# Display_Port.net
KiCad netlist of a schematic drawn in Altium Designer
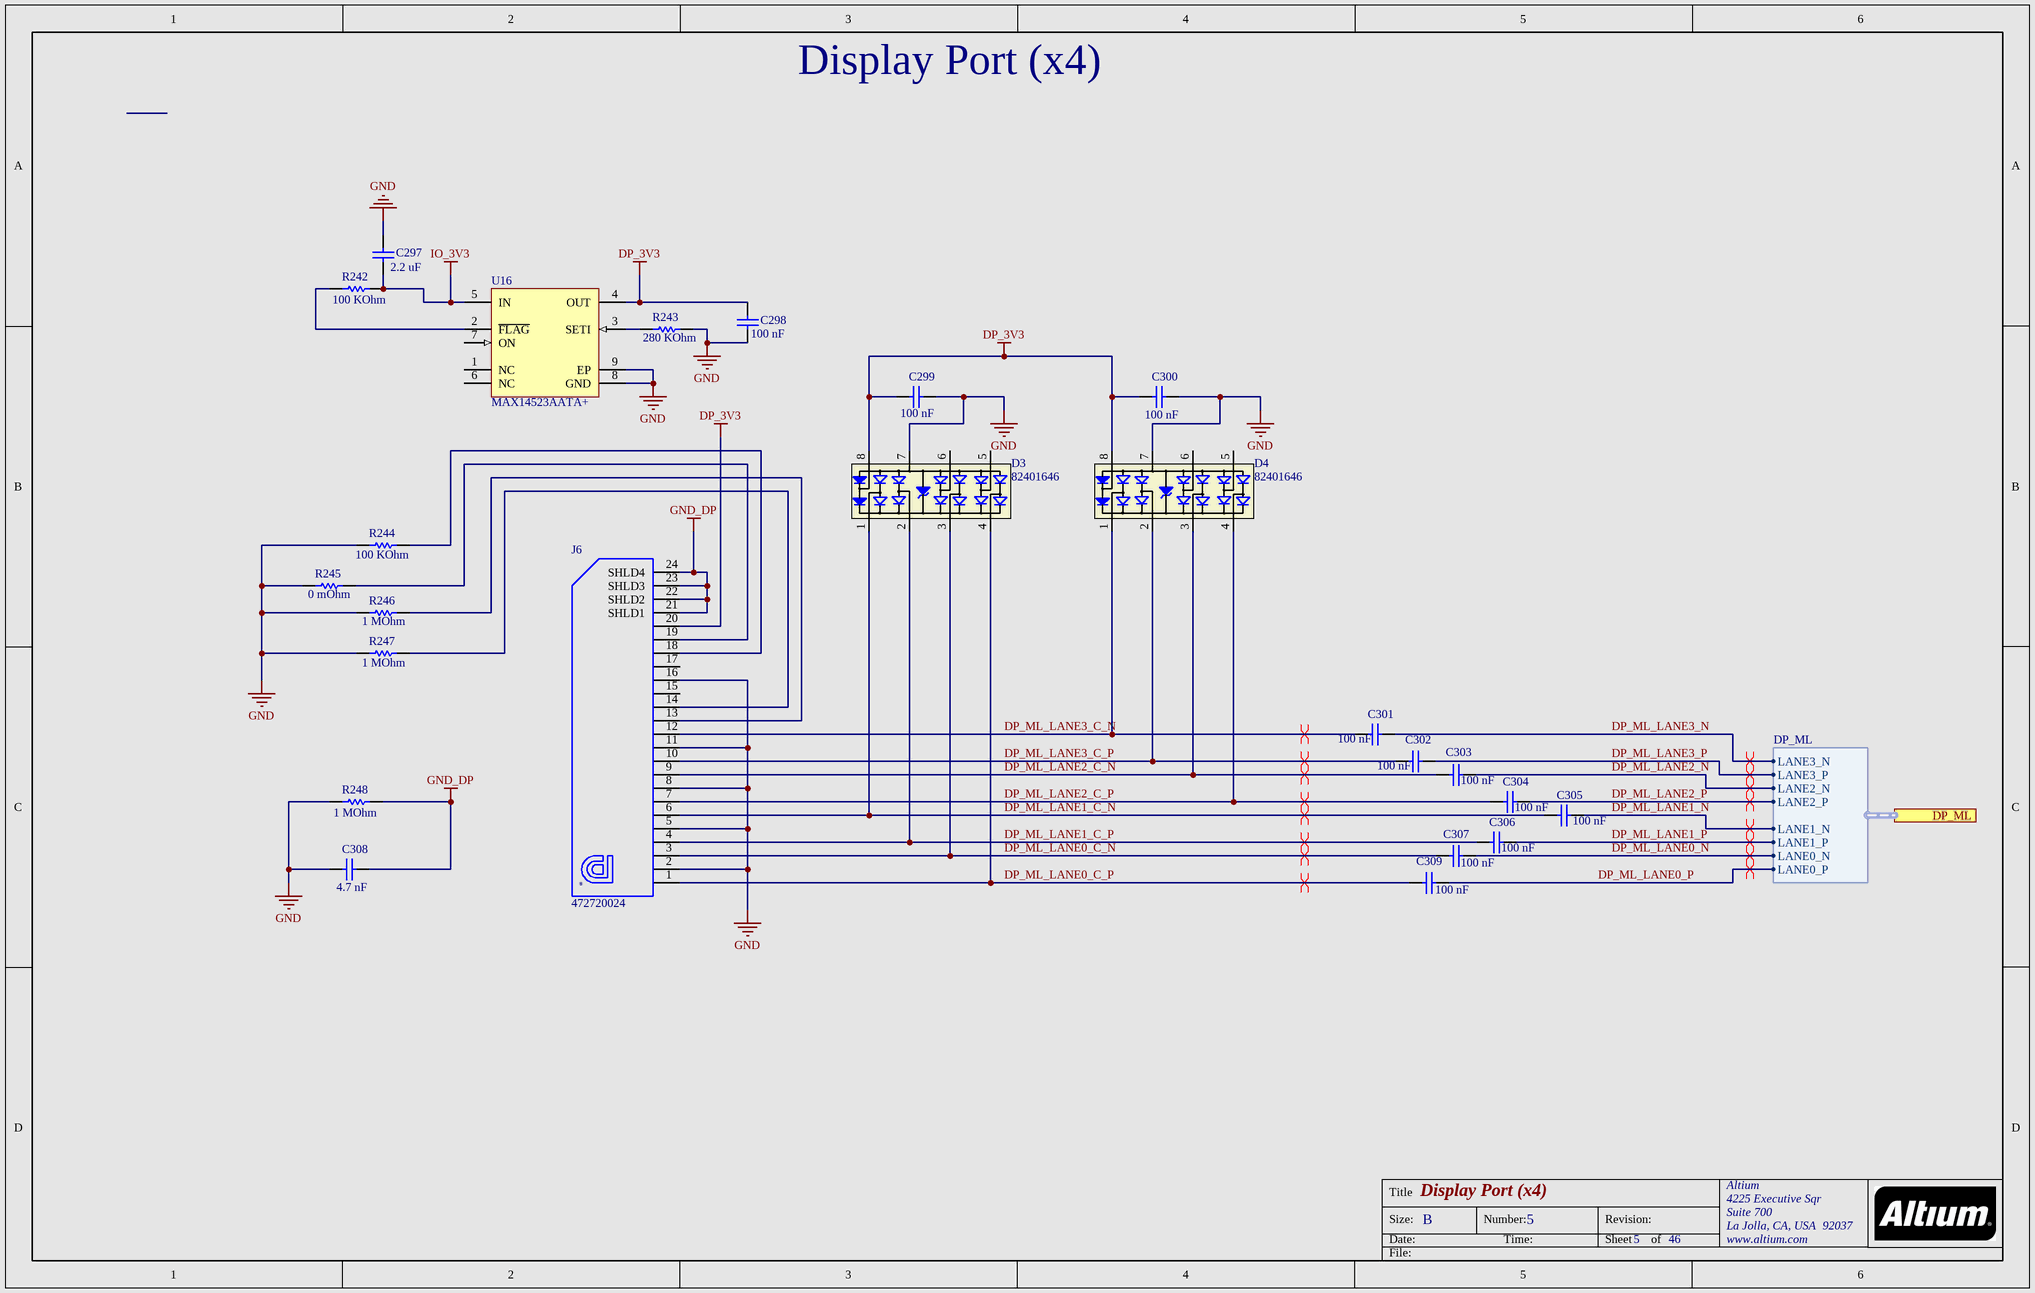
[diagram p0: Display_Port.SchDoc]

(export (version "E")
  (design (tool "Eeschema 10.0.6"))
  (components
    (comp (ref "C297")
      (value "GRM188R61A225KE34x")
      (footprint "CAPC1608X90X35ML10T15")
      (description "Chip Capacitor, 2.2 uF, +/- 10%, 10 V, -55 to 85 degC, 0603 (1608 Metric), RoHS, Tape and Reel")
      (fields (field (name "TOLERANCE") "10%") (field (name "CAPACITANCE") "2.2 uF"))
      (libsource (lib "") (part "CAP-NP-2_1"))
    )
    (comp (ref "C298")
      (value "C1005X7R1E104M")
      (footprint "CAPC1005X55X10LL05")
      (description "Chip Capacitor, 0.1 uF, +/- 20%, 25 V, -55 to 125 degC, 0402 (1005 Metric), RoHS, Tape and Reel")
      (fields (field (name "TOLERANCE") "20%") (field (name "CAPACITANCE") "100 nF"))
      (libsource (lib "Altium Content Vault") (part "CAP-NP-2"))
    )
    (comp (ref "C299")
      (value "C1005X7R1E104M")
      (footprint "CAPC1005X55X10LL05")
      (description "Chip Capacitor, 0.1 uF, +/- 20%, 25 V, -55 to 125 degC, 0402 (1005 Metric), RoHS, Tape and Reel")
      (fields (field (name "TOLERANCE") "20%") (field (name "CAPACITANCE") "100 nF"))
      (libsource (lib "Altium Content Vault") (part "CAP-NP-2"))
    )
    (comp (ref "C300")
      (value "C1005X7R1E104M")
      (footprint "CAPC1005X55X10LL05")
      (description "Chip Capacitor, 0.1 uF, +/- 20%, 25 V, -55 to 125 degC, 0402 (1005 Metric), RoHS, Tape and Reel")
      (fields (field (name "TOLERANCE") "20%") (field (name "CAPACITANCE") "100 nF"))
      (libsource (lib "Altium Content Vault") (part "CAP-NP-2"))
    )
    (comp (ref "C301")
      (value "C1005X7R1E104M")
      (footprint "CAPC1005X55X10LL05")
      (description "Chip Capacitor, 0.1 uF, +/- 20%, 25 V, -55 to 125 degC, 0402 (1005 Metric), RoHS, Tape and Reel")
      (fields (field (name "TOLERANCE") "20%") (field (name "CAPACITANCE") "100 nF"))
      (libsource (lib "Altium Content Vault") (part "CAP-NP-2"))
    )
    (comp (ref "C302")
      (value "C1005X7R1E104M")
      (footprint "CAPC1005X55X10LL05")
      (description "Chip Capacitor, 0.1 uF, +/- 20%, 25 V, -55 to 125 degC, 0402 (1005 Metric), RoHS, Tape and Reel")
      (fields (field (name "TOLERANCE") "20%") (field (name "CAPACITANCE") "100 nF"))
      (libsource (lib "Altium Content Vault") (part "CAP-NP-2"))
    )
    (comp (ref "C303")
      (value "C1005X7R1E104M")
      (footprint "CAPC1005X55X10LL05")
      (description "Chip Capacitor, 0.1 uF, +/- 20%, 25 V, -55 to 125 degC, 0402 (1005 Metric), RoHS, Tape and Reel")
      (fields (field (name "TOLERANCE") "20%") (field (name "CAPACITANCE") "100 nF"))
      (libsource (lib "Altium Content Vault") (part "CAP-NP-2"))
    )
    (comp (ref "C304")
      (value "C1005X7R1E104M")
      (footprint "CAPC1005X55X10LL05")
      (description "Chip Capacitor, 0.1 uF, +/- 20%, 25 V, -55 to 125 degC, 0402 (1005 Metric), RoHS, Tape and Reel")
      (fields (field (name "TOLERANCE") "20%") (field (name "CAPACITANCE") "100 nF"))
      (libsource (lib "Altium Content Vault") (part "CAP-NP-2"))
    )
    (comp (ref "C305")
      (value "C1005X7R1E104M")
      (footprint "CAPC1005X55X10LL05")
      (description "Chip Capacitor, 0.1 uF, +/- 20%, 25 V, -55 to 125 degC, 0402 (1005 Metric), RoHS, Tape and Reel")
      (fields (field (name "TOLERANCE") "20%") (field (name "CAPACITANCE") "100 nF"))
      (libsource (lib "Altium Content Vault") (part "CAP-NP-2"))
    )
    (comp (ref "C306")
      (value "C1005X7R1E104M")
      (footprint "CAPC1005X55X10LL05")
      (description "Chip Capacitor, 0.1 uF, +/- 20%, 25 V, -55 to 125 degC, 0402 (1005 Metric), RoHS, Tape and Reel")
      (fields (field (name "TOLERANCE") "20%") (field (name "CAPACITANCE") "100 nF"))
      (libsource (lib "Altium Content Vault") (part "CAP-NP-2"))
    )
    (comp (ref "C307")
      (value "C1005X7R1E104M")
      (footprint "CAPC1005X55X10LL05")
      (description "Chip Capacitor, 0.1 uF, +/- 20%, 25 V, -55 to 125 degC, 0402 (1005 Metric), RoHS, Tape and Reel")
      (fields (field (name "TOLERANCE") "20%") (field (name "CAPACITANCE") "100 nF"))
      (libsource (lib "Altium Content Vault") (part "CAP-NP-2"))
    )
    (comp (ref "C308")
      (value "GRM155R71H472KA01D")
      (footprint "CAPC1005X55X25NL05T10")
      (description "Chip Capacitor, 4.7 nF, +/- 10%, 50 V, -55 to 125 degC, 0402 (1005 Metric), RoHS, Tape and Reel")
      (fields
        (field (name "TOLERANCE") "10%")
        (field (name "CAPACITANCE") "4.7 nF")
        (field (name "MANUFACTURER") "Basic Passives")
      )
      (libsource (lib "Altium Content Vault") (part "CAP-NP-2"))
    )
    (comp (ref "C309")
      (value "C1005X7R1E104M")
      (footprint "CAPC1005X55X10LL05")
      (description "Chip Capacitor, 0.1 uF, +/- 20%, 25 V, -55 to 125 degC, 0402 (1005 Metric), RoHS, Tape and Reel")
      (fields (field (name "TOLERANCE") "20%") (field (name "CAPACITANCE") "100 nF"))
      (libsource (lib "Altium Content Vault") (part "CAP-NP-2"))
    )
    (comp (ref "D3")
      (value "82401646")
      (footprint "MSOP-8L")
      (description "TVS Diode WE-TVS-SS, VRWM=5V")
      (fields (field (name "MANUFACTURER") "Wuerth Elektronik"))
      (libsource (lib "Altium Content Vault") (part "CMP-1482-00002-1"))
    )
    (comp (ref "D4")
      (value "82401646")
      (footprint "MSOP-8L")
      (description "TVS Diode WE-TVS-SS, VRWM=5V")
      (fields (field (name "MANUFACTURER") "Wuerth Elektronik"))
      (libsource (lib "Altium Content Vault") (part "CMP-1482-00002-1"))
    )
    (comp (ref "J6")
      (value "472720024")
      (footprint "MOLX-472720024_V")
      (fields (field (name "MANUFACTURER") "Molex"))
      (libsource (lib "Altium Content Vault") (part "CMP-1704-00002-1"))
    )
    (comp (ref "R242")
      (value "ERJ-2RKF1003X")
      (footprint "RESC1005X40X25LL05T05")
      (description "Chip Resistor, 100 KOhm, +/- 1%, 100 mW, -55 to 155 degC, 0402 (1005 Metric), RoHS, Tape and Reel")
      (fields
        (field (name "RESISTANCE") "100 KOhm")
        (field (name "TOLERANCE") "1%")
        (field (name "MANUFACTURER") "Basic Passives")
      )
      (libsource (lib "Altium Content Vault") (part "RES-2"))
    )
    (comp (ref "R243")
      (value "ERJ-2RKF2803X")
      (footprint "RESC1005X40X25LL05T05")
      (description "Chip Resistor, 280 KOhm, +/- 1%, 100 mW, -55 to 155 degC, 0402 (1005 Metric), RoHS, Cut Tape")
      (fields
        (field (name "TOLERANCE") "1%")
        (field (name "RESISTANCE") "280 KOhm")
        (field (name "MANUFACTURER") "Basic Passives")
      )
      (libsource (lib "Altium Content Vault") (part "RES-2"))
    )
    (comp (ref "R244")
      (value "ERJ-2RKF1003X")
      (footprint "RESC1005X40X25LL05T05")
      (description "Chip Resistor, 100 KOhm, +/- 1%, 100 mW, -55 to 155 degC, 0402 (1005 Metric), RoHS, Tape and Reel")
      (fields
        (field (name "RESISTANCE") "100 KOhm")
        (field (name "TOLERANCE") "1%")
        (field (name "MANUFACTURER") "Basic Passives")
      )
      (libsource (lib "Altium Content Vault") (part "RES-2"))
    )
    (comp (ref "R245")
      (value "ERJ-2GE0R00X")
      (footprint "RESC1005X40X25ML05T05")
      (description "Chip Resistor, 0 mOhm, +/- 5%, 100 mW, -55 to 155 degC, 0402 (1005 Metric), RoHS, Tape and Reel")
      (fields
        (field (name "TOLERANCE") "5%")
        (field (name "RESISTANCE") "0 mOhm")
        (field (name "MANUFACTURER") "Basic Passives")
      )
      (libsource (lib "Altium Content Vault") (part "RES-2"))
    )
    (comp (ref "R246")
      (value "ERJ-2RKF1004X")
      (footprint "RESC1005X40X25LL05T05")
      (description "Chip Resistor, 1 MOhm, +/- 1%, 100 mW, -55 to 155 degC, 0402 (1005 Metric), RoHS, Tape and Reel")
      (fields
        (field (name "TOLERANCE") "1%")
        (field (name "RESISTANCE") "1 MOhm")
        (field (name "MANUFACTURER") "Basic Passives")
      )
      (libsource (lib "Altium Content Vault") (part "RES-2"))
    )
    (comp (ref "R247")
      (value "ERJ-2RKF1004X")
      (footprint "RESC1005X40X25LL05T05")
      (description "Chip Resistor, 1 MOhm, +/- 1%, 100 mW, -55 to 155 degC, 0402 (1005 Metric), RoHS, Tape and Reel")
      (fields
        (field (name "TOLERANCE") "1%")
        (field (name "RESISTANCE") "1 MOhm")
        (field (name "MANUFACTURER") "Basic Passives")
      )
      (libsource (lib "Altium Content Vault") (part "RES-2"))
    )
    (comp (ref "R248")
      (value "ERJ-2RKF1004X")
      (footprint "RESC1005X40X25LL05T05")
      (description "Chip Resistor, 1 MOhm, +/- 1%, 100 mW, -55 to 155 degC, 0402 (1005 Metric), RoHS, Tape and Reel")
      (fields
        (field (name "TOLERANCE") "1%")
        (field (name "RESISTANCE") "1 MOhm")
        (field (name "MANUFACTURER") "Basic Passives")
      )
      (libsource (lib "Altium Content Vault") (part "RES-2"))
    )
    (comp (ref "U16")
      (value "MAX14523AATA+")
      (footprint "MAXM-T833+2_V")
      (description "Adjustable Current-Limit Switch, 1.7 to 5.5 V, -40 to 125 degC, 8-Pin TDFN (T833+2), RoHS")
      (fields (field (name "MANUFACTURER") "Maxim"))
      (libsource (lib "Altium Content Vault") (part "MAXM-MAX14523A-T833+2-8"))
    )
  )
  (nets
    (net (code "2") (name "/DP_ML_LANE0_C_N") (class "Default")
      (node (ref "C307") (pin "2") (pinfunction "2_2") (pintype "passive"))
      (node (ref "D3") (pin "3") (pinfunction "I/O3_3") (pintype "passive"))
      (node (ref "J6") (pin "3") (pinfunction "3_3") (pintype "passive"))
    )
    (net (code "3") (name "/DP_ML_LANE0_C_P") (class "Default")
      (node (ref "C309") (pin "2") (pinfunction "2_2") (pintype "passive"))
      (node (ref "D3") (pin "4") (pinfunction "I/O4_4") (pintype "passive"))
      (node (ref "J6") (pin "1") (pinfunction "1_1") (pintype "passive"))
    )
    (net (code "4") (name "/DP_ML_LANE0_N") (class "Default")
      (node (ref "C307") (pin "1") (pinfunction "1_1") (pintype "passive"))
    )
    (net (code "5") (name "/DP_ML_LANE0_P") (class "Default")
      (node (ref "C309") (pin "1") (pinfunction "1_1") (pintype "passive"))
    )
    (net (code "6") (name "/DP_ML_LANE1_C_N") (class "Default")
      (node (ref "C305") (pin "2") (pinfunction "2_2") (pintype "passive"))
      (node (ref "D3") (pin "1") (pinfunction "I/O1_1") (pintype "passive"))
      (node (ref "J6") (pin "6") (pinfunction "6_6") (pintype "passive"))
    )
    (net (code "7") (name "/DP_ML_LANE1_C_P") (class "Default")
      (node (ref "C306") (pin "2") (pinfunction "2_2") (pintype "passive"))
      (node (ref "D3") (pin "2") (pinfunction "I/O2_2") (pintype "passive"))
      (node (ref "J6") (pin "4") (pinfunction "4_4") (pintype "passive"))
    )
    (net (code "8") (name "/DP_ML_LANE1_N") (class "Default")
      (node (ref "C305") (pin "1") (pinfunction "1_1") (pintype "passive"))
    )
    (net (code "9") (name "/DP_ML_LANE1_P") (class "Default")
      (node (ref "C306") (pin "1") (pinfunction "1_1") (pintype "passive"))
    )
    (net (code "10") (name "/DP_ML_LANE2_C_N") (class "Default")
      (node (ref "C303") (pin "2") (pinfunction "2_2") (pintype "passive"))
      (node (ref "D4") (pin "3") (pinfunction "I/O3_3") (pintype "passive"))
      (node (ref "J6") (pin "9") (pinfunction "9_9") (pintype "passive"))
    )
    (net (code "11") (name "/DP_ML_LANE2_C_P") (class "Default")
      (node (ref "C304") (pin "2") (pinfunction "2_2") (pintype "passive"))
      (node (ref "D4") (pin "4") (pinfunction "I/O4_4") (pintype "passive"))
      (node (ref "J6") (pin "7") (pinfunction "7_7") (pintype "passive"))
    )
    (net (code "12") (name "/DP_ML_LANE2_N") (class "Default")
      (node (ref "C303") (pin "1") (pinfunction "1_1") (pintype "passive"))
    )
    (net (code "13") (name "/DP_ML_LANE2_P") (class "Default")
      (node (ref "C304") (pin "1") (pinfunction "1_1") (pintype "passive"))
    )
    (net (code "14") (name "/DP_ML_LANE3_C_N") (class "Default")
      (node (ref "C301") (pin "2") (pinfunction "2_2") (pintype "passive"))
      (node (ref "D4") (pin "1") (pinfunction "I/O1_1") (pintype "passive"))
      (node (ref "J6") (pin "12") (pinfunction "12_12") (pintype "passive"))
    )
    (net (code "15") (name "/DP_ML_LANE3_C_P") (class "Default")
      (node (ref "C302") (pin "2") (pinfunction "2_2") (pintype "passive"))
      (node (ref "D4") (pin "2") (pinfunction "I/O2_2") (pintype "passive"))
      (node (ref "J6") (pin "10") (pinfunction "10_10") (pintype "passive"))
    )
    (net (code "16") (name "/DP_ML_LANE3_N") (class "Default")
      (node (ref "C301") (pin "1") (pinfunction "1_1") (pintype "passive"))
    )
    (net (code "17") (name "/DP_ML_LANE3_P") (class "Default")
      (node (ref "C302") (pin "1") (pinfunction "1_1") (pintype "passive"))
    )
    (net (code "19") (name "DP_3V3") (class "Default")
      (node (ref "C298") (pin "2") (pinfunction "2_2") (pintype "passive"))
      (node (ref "C299") (pin "2") (pinfunction "2_2") (pintype "passive"))
      (node (ref "C300") (pin "2") (pinfunction "2_2") (pintype "passive"))
      (node (ref "D3") (pin "8") (pinfunction "VDD_8") (pintype "passive"))
      (node (ref "D4") (pin "8") (pinfunction "VDD_8") (pintype "passive"))
      (node (ref "J6") (pin "20") (pinfunction "20_20") (pintype "passive"))
      (node (ref "U16") (pin "4") (pinfunction "OUT_4") (pintype "power_in"))
    )
    (net (code "20") (name "GND") (class "Default")
      (node (ref "C297") (pin "2") (pinfunction "2_2") (pintype "passive"))
      (node (ref "C298") (pin "1") (pinfunction "1_1") (pintype "passive"))
      (node (ref "C299") (pin "1") (pinfunction "1_1") (pintype "passive"))
      (node (ref "C300") (pin "1") (pinfunction "1_1") (pintype "passive"))
      (node (ref "C308") (pin "1") (pinfunction "1_1") (pintype "passive"))
      (node (ref "D3") (pin "7") (pinfunction "GND_7") (pintype "passive"))
      (node (ref "D4") (pin "7") (pinfunction "GND_7") (pintype "passive"))
      (node (ref "J6") (pin "11") (pinfunction "11_11") (pintype "passive"))
      (node (ref "J6") (pin "16") (pinfunction "16_16") (pintype "passive"))
      (node (ref "J6") (pin "2") (pinfunction "2_2") (pintype "passive"))
      (node (ref "J6") (pin "5") (pinfunction "5_5") (pintype "passive"))
      (node (ref "J6") (pin "8") (pinfunction "8_8") (pintype "passive"))
      (node (ref "R243") (pin "2") (pinfunction "2_2") (pintype "passive"))
      (node (ref "R244") (pin "1") (pinfunction "1_1") (pintype "passive"))
      (node (ref "R245") (pin "1") (pinfunction "1_1") (pintype "passive"))
      (node (ref "R246") (pin "1") (pinfunction "1_1") (pintype "passive"))
      (node (ref "R247") (pin "1") (pinfunction "1_1") (pintype "passive"))
      (node (ref "R248") (pin "1") (pinfunction "1_1") (pintype "passive"))
      (node (ref "U16") (pin "8") (pinfunction "GND_8") (pintype "power_in"))
      (node (ref "U16") (pin "9") (pinfunction "EP_9") (pintype "power_in"))
    )
    (net (code "21") (name "GND_DP") (class "Default")
      (node (ref "C308") (pin "2") (pinfunction "2_2") (pintype "passive"))
      (node (ref "J6") (pin "21") (pinfunction "SHLD1_21") (pintype "passive"))
      (node (ref "J6") (pin "22") (pinfunction "SHLD2_22") (pintype "passive"))
      (node (ref "J6") (pin "23") (pinfunction "SHLD3_23") (pintype "passive"))
      (node (ref "J6") (pin "24") (pinfunction "SHLD4_24") (pintype "passive"))
      (node (ref "R248") (pin "2") (pinfunction "2_2") (pintype "passive"))
    )
    (net (code "22") (name "IO_3V3") (class "Default")
      (node (ref "C297") (pin "1") (pinfunction "1_1") (pintype "passive"))
      (node (ref "R242") (pin "2") (pinfunction "2_2") (pintype "passive"))
      (node (ref "U16") (pin "5") (pinfunction "IN_5") (pintype "power_in"))
    )
    (net (code "23") (name "Net-(J6-Pad13)") (class "Default")
      (node (ref "J6") (pin "13") (pinfunction "13_13") (pintype "passive"))
      (node (ref "R246") (pin "2") (pinfunction "2_2") (pintype "passive"))
    )
    (net (code "24") (name "Net-(J6-Pad14)") (class "Default")
      (node (ref "J6") (pin "14") (pinfunction "14_14") (pintype "passive"))
      (node (ref "R247") (pin "2") (pinfunction "2_2") (pintype "passive"))
    )
    (net (code "25") (name "Net-(J6-Pad18)") (class "Default")
      (node (ref "J6") (pin "18") (pinfunction "18_18") (pintype "passive"))
      (node (ref "R244") (pin "2") (pinfunction "2_2") (pintype "passive"))
    )
    (net (code "26") (name "Net-(J6-Pad19)") (class "Default")
      (node (ref "J6") (pin "19") (pinfunction "19_19") (pintype "passive"))
      (node (ref "R245") (pin "2") (pinfunction "2_2") (pintype "passive"))
    )
    (net (code "27") (name "Net-(U16-SETI)") (class "Default")
      (node (ref "R243") (pin "1") (pinfunction "1_1") (pintype "passive"))
      (node (ref "U16") (pin "3") (pinfunction "SETI_3") (pintype "input"))
    )
    (net (code "28") (name "Net-(U16-~{FLAG})") (class "Default")
      (node (ref "R242") (pin "1") (pinfunction "1_1") (pintype "passive"))
      (node (ref "U16") (pin "2") (pinfunction "~{FLAG}_2") (pintype "open_collector"))
    )
    (net (code "29") (name "unconnected-(D3-I{slash}O5-Pad5)") (class "Default")
      (node (ref "D3") (pin "5") (pinfunction "I/O5_5") (pintype "passive"))
    )
    (net (code "30") (name "unconnected-(D3-I{slash}O6-Pad6)") (class "Default")
      (node (ref "D3") (pin "6") (pinfunction "I/O6_6") (pintype "passive"))
    )
    (net (code "31") (name "unconnected-(D4-I{slash}O5-Pad5)") (class "Default")
      (node (ref "D4") (pin "5") (pinfunction "I/O5_5") (pintype "passive"))
    )
    (net (code "32") (name "unconnected-(D4-I{slash}O6-Pad6)") (class "Default")
      (node (ref "D4") (pin "6") (pinfunction "I/O6_6") (pintype "passive"))
    )
    (net (code "33") (name "unconnected-(J6-Pad15)") (class "Default")
      (node (ref "J6") (pin "15") (pinfunction "15_15") (pintype "passive"))
    )
    (net (code "34") (name "unconnected-(J6-Pad17)") (class "Default")
      (node (ref "J6") (pin "17") (pinfunction "17_17") (pintype "passive"))
    )
    (net (code "35") (name "unconnected-(U16-NC-Pad1)") (class "Default")
      (node (ref "U16") (pin "1") (pinfunction "NC_1") (pintype "passive"))
    )
    (net (code "36") (name "unconnected-(U16-NC-Pad6)") (class "Default")
      (node (ref "U16") (pin "6") (pinfunction "NC_6") (pintype "passive"))
    )
    (net (code "37") (name "unconnected-(U16-ON-Pad7)") (class "Default")
      (node (ref "U16") (pin "7") (pinfunction "ON_7") (pintype "input"))
    )
  )
)
